# MUX.net
KiCad netlist of a schematic drawn in Altium Designer
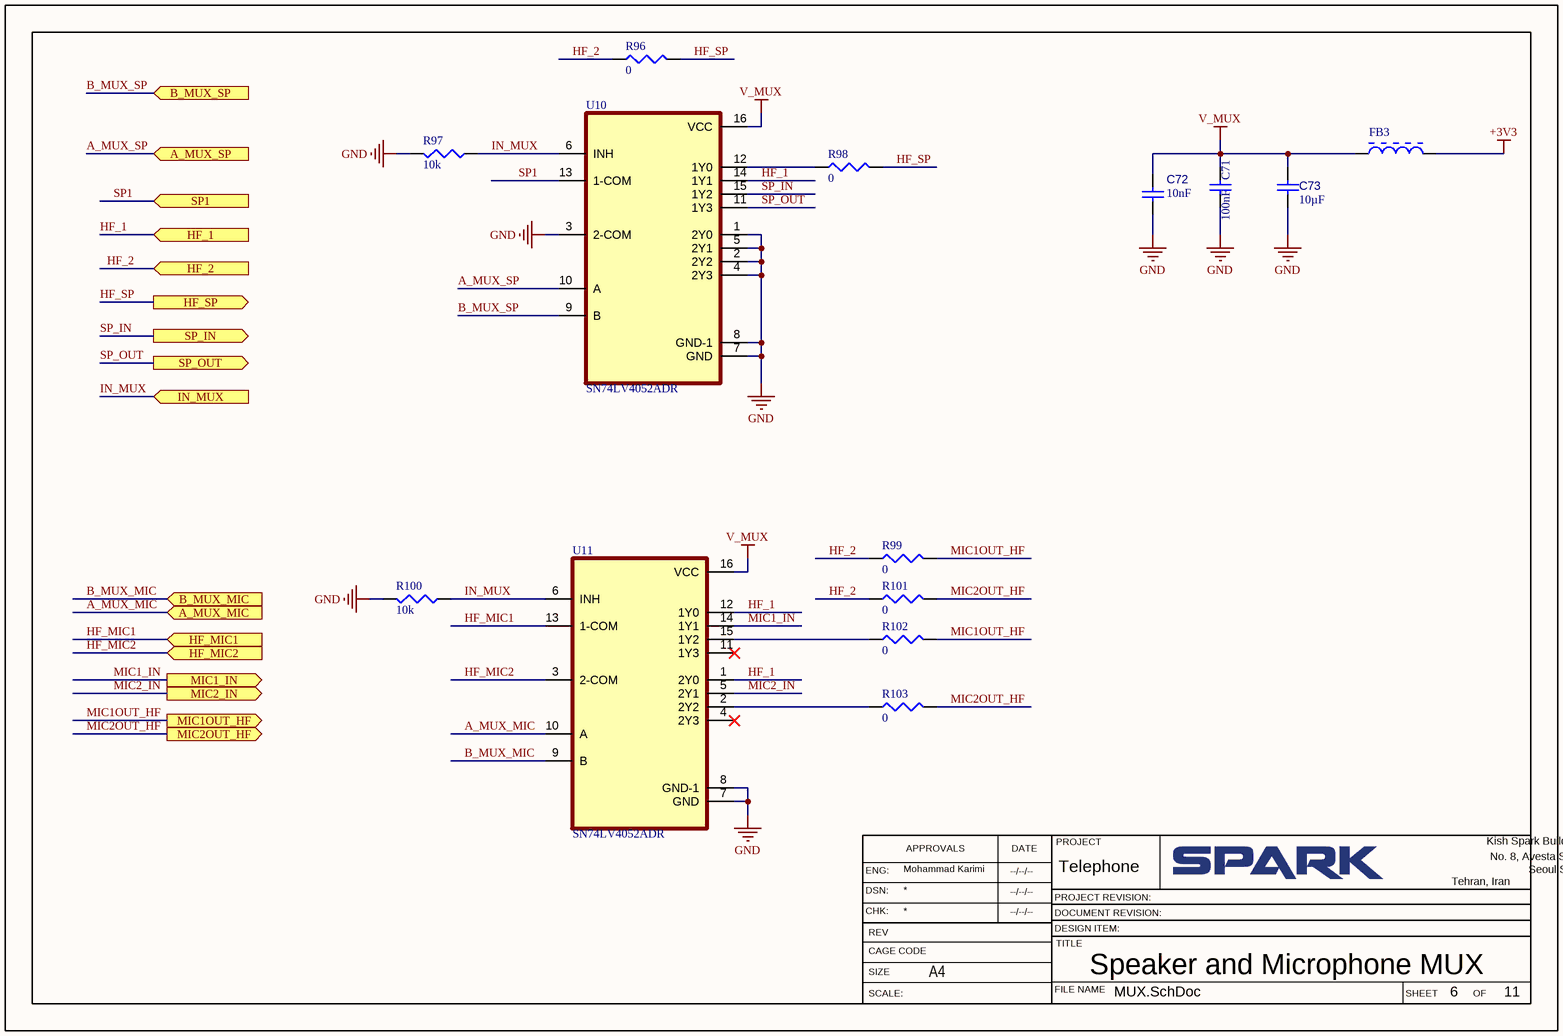
[diagram p0: MUX.SchDoc]

(export (version "E")
  (design (tool "Eeschema 10.0.6"))
  (components
    (comp (ref "C71")
      (value "100nF")
      (footprint "C0603")
      (description "YAGEO - CC0603KRX7R8BB104 - CERAMIC CAPACITOR, 0.1UF, 25V, X7R, 10%, 0603, FULL REEL")
      (fields
        (field (name "TOLERANCE") "10%")
        (field (name "VOLTAGE") "25V")
        (field (name "SOURCE") "PTZLib.SchLib")
      )
      (libsource (lib "Kish Spark") (part "CAP-NP-2"))
    )
    (comp (ref "C72")
      (value "10nF")
      (footprint "C0603")
      (description "0603 10nF 50 V ±10 % Tolerance X7R Surface Mount Multilayer Ceramic Capacitor")
      (fields (field (name "TOLERANCE") "10%") (field (name "MANUFACTURER") "Kyocera AVX"))
      (libsource (lib "Kish Spark") (part "CAP-NP-2"))
    )
    (comp (ref "C73")
      (value "10µF")
      (footprint "0805")
      (description "Ceramic Capacitor, 10UF, 6.3V, X5R, 10%, 0805, Full Reel")
      (fields
        (field (name "MANUFACTURER") "KEMET")
        (field (name "MANUFACTURER PART NUMBER") "C0805C106K9PACTU")
      )
      (libsource (lib "Kish Spark") (part "CAP-NP-2"))
    )
    (comp (ref "FB3")
      (value "CMP-006-00051-1")
      (footprint "R0603")
      (description "Ferrite Beads 0603 60ohm")
      (fields (field (name "TOLERANCE") "25%") (field (name "SOURCE") "PTZLib.SchLib"))
      (libsource (lib "Kish Spark") (part "FerriteBead"))
    )
    (comp (ref "R96")
      (value "0")
      (footprint "R0603")
      (description "Res Thkflm 0603 0 Ohm Jumper 1/10W 100Ppm/ C Smd Rohs Compliant: Yes")
      (fields (field (name "Comment") "RMCF0603ZT0R00") (field (name "SOURCE") "PTZLib.SchLib"))
      (libsource (lib "Kish Spark") (part "CRCW060349R9FKEAC"))
    )
    (comp (ref "R97")
      (value "10k")
      (footprint "R0603")
      (description "Res Thick Film 0603 10K Ohm 5% 1/10W 200ppm/C Molded SMD SMD Paper T/R")
      (fields
        (field (name "TOLERANCE") "5%")
        (field (name "Comment") "CRCW060310K0JNEA")
        (field (name "SOURCE") "PTZLib.SchLib")
      )
      (libsource (lib "Kish Spark") (part "RN73R1JTTD3302F10"))
    )
    (comp (ref "R98")
      (value "0")
      (footprint "R0603")
      (description "Res Thkflm 0603 0 Ohm Jumper 1/10W 100Ppm/ C Smd Rohs Compliant: Yes")
      (fields (field (name "Comment") "RMCF0603ZT0R00") (field (name "SOURCE") "PTZLib.SchLib"))
      (libsource (lib "Kish Spark") (part "CRCW060349R9FKEAC"))
    )
    (comp (ref "R99")
      (value "0")
      (footprint "R0603")
      (description "Res Thkflm 0603 0 Ohm Jumper 1/10W 100Ppm/ C Smd Rohs Compliant: Yes")
      (fields (field (name "Comment") "RMCF0603ZT0R00") (field (name "SOURCE") "PTZLib.SchLib"))
      (libsource (lib "Kish Spark") (part "CRCW060349R9FKEAC"))
    )
    (comp (ref "R100")
      (value "10k")
      (footprint "R0603")
      (description "Res Thick Film 0603 10K Ohm 5% 1/10W 200ppm/C Molded SMD SMD Paper T/R")
      (fields
        (field (name "TOLERANCE") "5%")
        (field (name "Comment") "CRCW060310K0JNEA")
        (field (name "SOURCE") "PTZLib.SchLib")
      )
      (libsource (lib "Kish Spark") (part "RN73R1JTTD3302F10"))
    )
    (comp (ref "R101")
      (value "0")
      (footprint "R0603")
      (description "Res Thkflm 0603 0 Ohm Jumper 1/10W 100Ppm/ C Smd Rohs Compliant: Yes")
      (fields (field (name "Comment") "RMCF0603ZT0R00") (field (name "SOURCE") "PTZLib.SchLib"))
      (libsource (lib "Kish Spark") (part "CRCW060349R9FKEAC"))
    )
    (comp (ref "R102")
      (value "0")
      (footprint "R0603")
      (description "Res Thkflm 0603 0 Ohm Jumper 1/10W 100Ppm/ C Smd Rohs Compliant: Yes")
      (fields (field (name "Comment") "RMCF0603ZT0R00") (field (name "SOURCE") "PTZLib.SchLib"))
      (libsource (lib "Kish Spark") (part "CRCW060349R9FKEAC"))
    )
    (comp (ref "R103")
      (value "0")
      (footprint "R0603")
      (description "Res Thkflm 0603 0 Ohm Jumper 1/10W 100Ppm/ C Smd Rohs Compliant: Yes")
      (fields (field (name "Comment") "RMCF0603ZT0R00") (field (name "SOURCE") "PTZLib.SchLib"))
      (libsource (lib "Kish Spark") (part "CRCW060349R9FKEAC"))
    )
    (comp (ref "U10")
      (value "SN74LV4052ADR")
      (footprint "demultiplexer")
      (description "IC MULTIPLEXER DUAL 4X1 16SOIC")
      (fields (field (name "MANUFACTURER") "Texas Instruments"))
      (libsource (lib "Kish Spark") (part "SN74LV4052ADR"))
    )
    (comp (ref "U11")
      (value "SN74LV4052ADR")
      (footprint "demultiplexer")
      (description "IC MULTIPLEXER DUAL 4X1 16SOIC")
      (fields (field (name "MANUFACTURER") "Texas Instruments"))
      (libsource (lib "Kish Spark") (part "SN74LV4052ADR"))
    )
  )
  (nets
    (net (code "1") (name "+3V3") (class "Default")
      (node (ref "FB3") (pin "2") (pinfunction "2_2") (pintype "passive"))
    )
    (net (code "2") (name "/A_MUX_MIC") (class "Default")
      (node (ref "U11") (pin "10") (pinfunction "A_10") (pintype "passive"))
    )
    (net (code "3") (name "/A_MUX_SP") (class "Default")
      (node (ref "U10") (pin "10") (pinfunction "A_10") (pintype "passive"))
    )
    (net (code "4") (name "/B_MUX_MIC") (class "Default")
      (node (ref "U11") (pin "9") (pinfunction "B_9") (pintype "passive"))
    )
    (net (code "5") (name "/B_MUX_SP") (class "Default")
      (node (ref "U10") (pin "9") (pinfunction "B_9") (pintype "passive"))
    )
    (net (code "6") (name "/HF_1") (class "Default")
      (node (ref "U10") (pin "14") (pinfunction "1Y1_14") (pintype "passive"))
      (node (ref "U11") (pin "1") (pinfunction "2Y0_1") (pintype "passive"))
      (node (ref "U11") (pin "12") (pinfunction "1Y0_12") (pintype "passive"))
    )
    (net (code "7") (name "/HF_2") (class "Default")
      (node (ref "R101") (pin "1") (pinfunction "1_1") (pintype "passive"))
      (node (ref "R96") (pin "1") (pinfunction "1_1") (pintype "passive"))
      (node (ref "R99") (pin "1") (pinfunction "1_1") (pintype "passive"))
    )
    (net (code "8") (name "/HF_MIC1") (class "Default")
      (node (ref "U11") (pin "13") (pinfunction "1-COM_13") (pintype "passive"))
    )
    (net (code "9") (name "/HF_MIC2") (class "Default")
      (node (ref "U11") (pin "3") (pinfunction "2-COM_3") (pintype "passive"))
    )
    (net (code "10") (name "/HF_SP") (class "Default")
      (node (ref "R96") (pin "2") (pinfunction "2_2") (pintype "passive"))
      (node (ref "R98") (pin "2") (pinfunction "2_2") (pintype "passive"))
    )
    (net (code "11") (name "/IN_MUX") (class "Default")
      (node (ref "R100") (pin "1") (pinfunction "1_1") (pintype "passive"))
      (node (ref "R97") (pin "1") (pinfunction "1_1") (pintype "passive"))
      (node (ref "U10") (pin "6") (pinfunction "INH_6") (pintype "passive"))
      (node (ref "U11") (pin "6") (pinfunction "INH_6") (pintype "passive"))
    )
    (net (code "12") (name "/MIC1OUT_HF") (class "Default")
      (node (ref "R102") (pin "2") (pinfunction "2_2") (pintype "passive"))
      (node (ref "R99") (pin "2") (pinfunction "2_2") (pintype "passive"))
    )
    (net (code "13") (name "/MIC1_IN") (class "Default")
      (node (ref "U11") (pin "14") (pinfunction "1Y1_14") (pintype "passive"))
    )
    (net (code "14") (name "/MIC2OUT_HF") (class "Default")
      (node (ref "R101") (pin "2") (pinfunction "2_2") (pintype "passive"))
      (node (ref "R103") (pin "2") (pinfunction "2_2") (pintype "passive"))
    )
    (net (code "15") (name "/MIC2_IN") (class "Default")
      (node (ref "U11") (pin "5") (pinfunction "2Y1_5") (pintype "passive"))
    )
    (net (code "16") (name "/SP1") (class "Default")
      (node (ref "U10") (pin "13") (pinfunction "1-COM_13") (pintype "passive"))
    )
    (net (code "17") (name "/SP_IN") (class "Default")
      (node (ref "U10") (pin "15") (pinfunction "1Y2_15") (pintype "passive"))
    )
    (net (code "18") (name "/SP_OUT") (class "Default")
      (node (ref "U10") (pin "11") (pinfunction "1Y3_11") (pintype "passive"))
    )
    (net (code "19") (name "GND") (class "Default")
      (node (ref "C71") (pin "2") (pinfunction "2_2") (pintype "passive"))
      (node (ref "C72") (pin "1") (pinfunction "1_1") (pintype "passive"))
      (node (ref "C73") (pin "1") (pinfunction "1_1") (pintype "passive"))
      (node (ref "R100") (pin "2") (pinfunction "2_2") (pintype "passive"))
      (node (ref "R97") (pin "2") (pinfunction "2_2") (pintype "passive"))
      (node (ref "U10") (pin "1") (pinfunction "2Y0_1") (pintype "passive"))
      (node (ref "U10") (pin "2") (pinfunction "2Y2_2") (pintype "passive"))
      (node (ref "U10") (pin "3") (pinfunction "2-COM_3") (pintype "passive"))
      (node (ref "U10") (pin "4") (pinfunction "2Y3_4") (pintype "passive"))
      (node (ref "U10") (pin "5") (pinfunction "2Y1_5") (pintype "passive"))
      (node (ref "U10") (pin "7") (pinfunction "GND_7") (pintype "power_in"))
      (node (ref "U10") (pin "8") (pinfunction "GND-1_8") (pintype "power_in"))
      (node (ref "U11") (pin "7") (pinfunction "GND_7") (pintype "power_in"))
      (node (ref "U11") (pin "8") (pinfunction "GND-1_8") (pintype "power_in"))
    )
    (net (code "20") (name "Net-(U10-1Y0)") (class "Default")
      (node (ref "R98") (pin "1") (pinfunction "1_1") (pintype "passive"))
      (node (ref "U10") (pin "12") (pinfunction "1Y0_12") (pintype "passive"))
    )
    (net (code "21") (name "Net-(U11-1Y2)") (class "Default")
      (node (ref "R102") (pin "1") (pinfunction "1_1") (pintype "passive"))
      (node (ref "U11") (pin "15") (pinfunction "1Y2_15") (pintype "passive"))
    )
    (net (code "22") (name "Net-(U11-2Y2)") (class "Default")
      (node (ref "R103") (pin "1") (pinfunction "1_1") (pintype "passive"))
      (node (ref "U11") (pin "2") (pinfunction "2Y2_2") (pintype "passive"))
    )
    (net (code "23") (name "V_MUX") (class "Default")
      (node (ref "C71") (pin "1") (pinfunction "1_1") (pintype "passive"))
      (node (ref "C72") (pin "2") (pinfunction "2_2") (pintype "passive"))
      (node (ref "C73") (pin "2") (pinfunction "2_2") (pintype "passive"))
      (node (ref "FB3") (pin "1") (pinfunction "1_1") (pintype "passive"))
      (node (ref "U10") (pin "16") (pinfunction "VCC_16") (pintype "power_in"))
      (node (ref "U11") (pin "16") (pinfunction "VCC_16") (pintype "power_in"))
    )
    (net (code "24") (name "unconnected-(U11-1Y3-Pad11)") (class "Default")
      (node (ref "U11") (pin "11") (pinfunction "1Y3_11") (pintype "passive+no_connect"))
    )
    (net (code "25") (name "unconnected-(U11-2Y3-Pad4)") (class "Default")
      (node (ref "U11") (pin "4") (pinfunction "2Y3_4") (pintype "passive+no_connect"))
    )
  )
)
